# C210_0001_Serial_Interface.net
KiCad netlist of a schematic drawn in Altium Designer
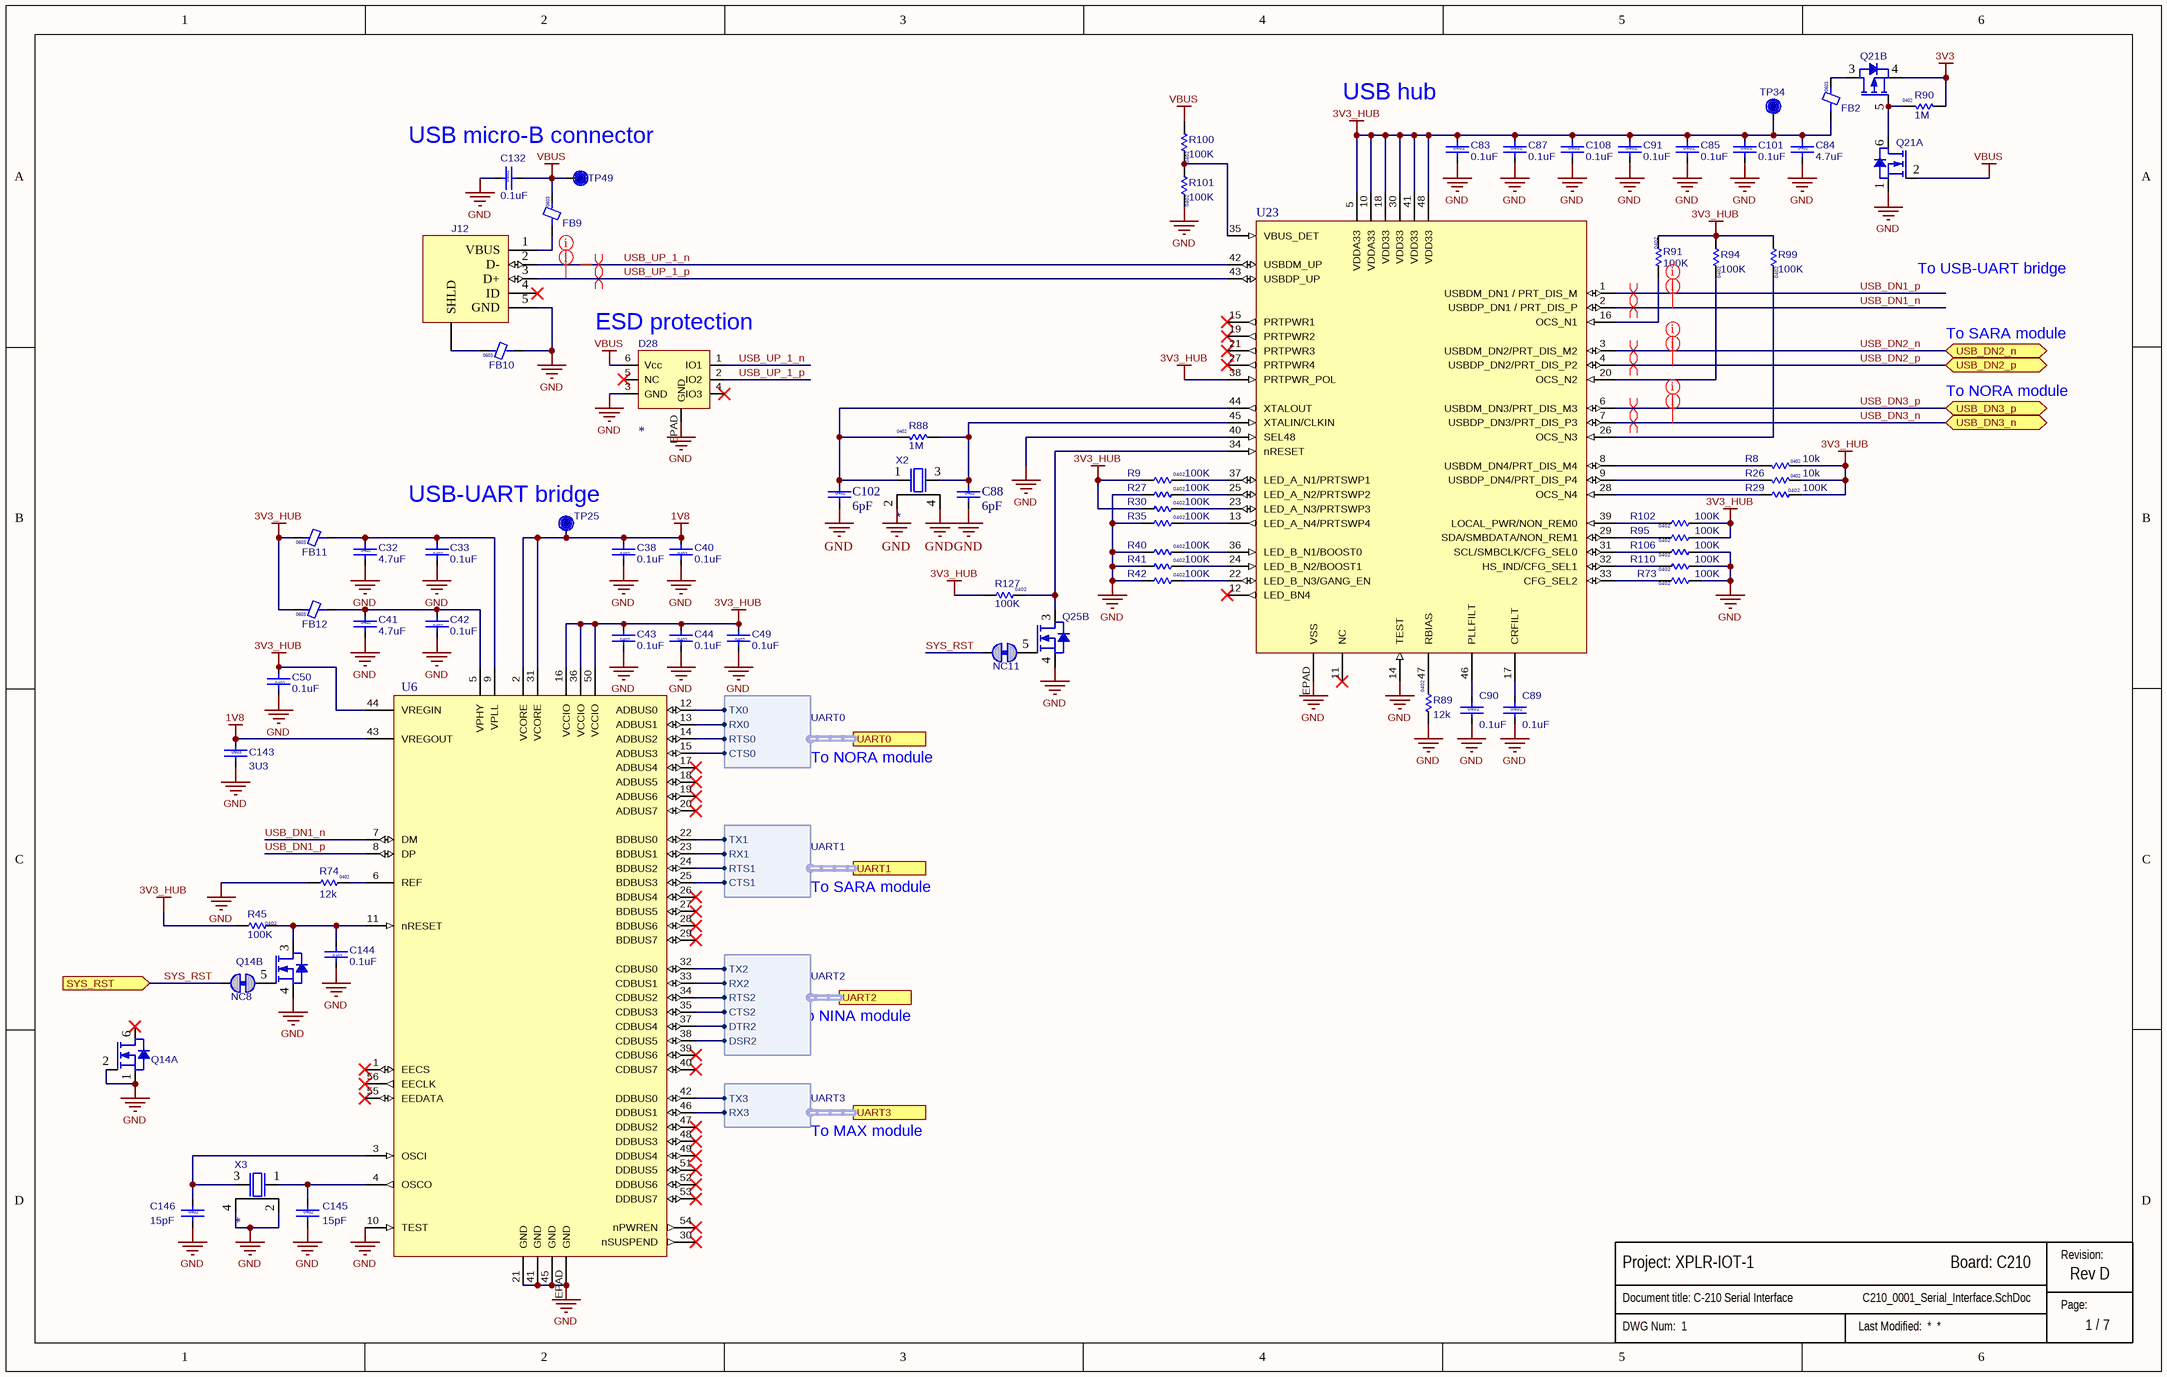
[diagram p0: C210_0001_Serial_Interface.SchDoc]

(export (version "E")
  (design (tool "Eeschema 10.0.6"))
  (components
    (comp (ref "C32")
      (value "4.7uF")
      (footprint "Cap 0402 HD")
      (description "Cap, Ceramic 4.7uF 10V 20% X5R 0402")
      (fields
        (field (name "SIZE") "0402")
        (field (name "PART NUMBER") "120-00020")
        (field (name "TOLERANCE") "+/- 20%")
      )
      (libsource (lib "Arena_Parts_DB_Lib") (part "Cap Chip"))
    )
    (comp (ref "C33")
      (value "0.1uF")
      (footprint "Cap 0402 HD")
      (description "Cap, Ceramic 0.1uF 10V 10% X5R 0402")
      (fields
        (field (name "SIZE") "0402")
        (field (name "PART NUMBER") "120-00016")
        (field (name "MANUFACTURER") "Murata Electronics North America")
      )
      (libsource (lib "Arena_Parts_DB_Lib") (part "Cap Chip"))
    )
    (comp (ref "C38")
      (value "0.1uF")
      (footprint "Cap 0402 HD")
      (description "Cap, Ceramic 0.1uF 10V 10% X5R 0402")
      (fields
        (field (name "SIZE") "0402")
        (field (name "PART NUMBER") "120-00016")
        (field (name "MANUFACTURER") "Murata Electronics North America")
      )
      (libsource (lib "Arena_Parts_DB_Lib") (part "Cap Chip"))
    )
    (comp (ref "C40")
      (value "0.1uF")
      (footprint "Cap 0402 HD")
      (description "Cap, Ceramic 0.1uF 10V 10% X5R 0402")
      (fields
        (field (name "SIZE") "0402")
        (field (name "PART NUMBER") "120-00016")
        (field (name "MANUFACTURER") "Murata Electronics North America")
      )
      (libsource (lib "Arena_Parts_DB_Lib") (part "Cap Chip"))
    )
    (comp (ref "C41")
      (value "4.7uF")
      (footprint "Cap 0402 HD")
      (description "Cap, Ceramic 4.7uF 10V 20% X5R 0402")
      (fields
        (field (name "SIZE") "0402")
        (field (name "PART NUMBER") "120-00020")
        (field (name "TOLERANCE") "+/- 20%")
      )
      (libsource (lib "Arena_Parts_DB_Lib") (part "Cap Chip"))
    )
    (comp (ref "C42")
      (value "0.1uF")
      (footprint "Cap 0402 HD")
      (description "Cap, Ceramic 0.1uF 10V 10% X5R 0402")
      (fields
        (field (name "SIZE") "0402")
        (field (name "PART NUMBER") "120-00016")
        (field (name "MANUFACTURER") "Murata Electronics North America")
      )
      (libsource (lib "Arena_Parts_DB_Lib") (part "Cap Chip"))
    )
    (comp (ref "C43")
      (value "0.1uF")
      (footprint "Cap 0402 HD")
      (description "Cap, Ceramic 0.1uF 10V 10% X5R 0402")
      (fields
        (field (name "SIZE") "0402")
        (field (name "PART NUMBER") "120-00016")
        (field (name "MANUFACTURER") "Murata Electronics North America")
      )
      (libsource (lib "Arena_Parts_DB_Lib") (part "Cap Chip"))
    )
    (comp (ref "C44")
      (value "0.1uF")
      (footprint "Cap 0402 HD")
      (description "Cap, Ceramic 0.1uF 10V 10% X5R 0402")
      (fields
        (field (name "SIZE") "0402")
        (field (name "PART NUMBER") "120-00016")
        (field (name "MANUFACTURER") "Murata Electronics North America")
      )
      (libsource (lib "Arena_Parts_DB_Lib") (part "Cap Chip"))
    )
    (comp (ref "C49")
      (value "0.1uF")
      (footprint "Cap 0402 HD")
      (description "Cap, Ceramic 0.1uF 10V 10% X5R 0402")
      (fields
        (field (name "SIZE") "0402")
        (field (name "PART NUMBER") "120-00016")
        (field (name "MANUFACTURER") "Murata Electronics North America")
      )
      (libsource (lib "Arena_Parts_DB_Lib") (part "Cap Chip"))
    )
    (comp (ref "C50")
      (value "0.1uF")
      (footprint "Cap 0402 HD")
      (description "Cap, Ceramic 0.1uF 10V 10% X5R 0402")
      (fields
        (field (name "SIZE") "0402")
        (field (name "PART NUMBER") "120-00016")
        (field (name "MANUFACTURER") "Murata Electronics North America")
      )
      (libsource (lib "Arena_Parts_DB_Lib") (part "Cap Chip"))
    )
    (comp (ref "C83")
      (value "0.1uF")
      (footprint "Cap 0402 HD")
      (description "Cap, Ceramic 0.1uF 10V 10% X5R 0402")
      (fields
        (field (name "SIZE") "0402")
        (field (name "PART NUMBER") "120-00016")
        (field (name "MANUFACTURER") "Murata Electronics North America")
      )
      (libsource (lib "Arena_Parts_DB_Lib") (part "Cap Chip"))
    )
    (comp (ref "C84")
      (value "4.7uF")
      (footprint "Cap 0402 HD")
      (description "Cap, Ceramic 4.7uF 10V 20% X5R 0402")
      (fields
        (field (name "SIZE") "0402")
        (field (name "PART NUMBER") "120-00020")
        (field (name "TOLERANCE") "+/- 20%")
      )
      (libsource (lib "Arena_Parts_DB_Lib") (part "Cap Chip"))
    )
    (comp (ref "C85")
      (value "0.1uF")
      (footprint "Cap 0402 HD")
      (description "Cap, Ceramic 0.1uF 10V 10% X5R 0402")
      (fields
        (field (name "SIZE") "0402")
        (field (name "PART NUMBER") "120-00016")
        (field (name "MANUFACTURER") "Murata Electronics North America")
      )
      (libsource (lib "Arena_Parts_DB_Lib") (part "Cap Chip"))
    )
    (comp (ref "C87")
      (value "0.1uF")
      (footprint "Cap 0402 HD")
      (description "Cap, Ceramic 0.1uF 10V 10% X5R 0402")
      (fields
        (field (name "SIZE") "0402")
        (field (name "PART NUMBER") "120-00016")
        (field (name "MANUFACTURER") "Murata Electronics North America")
      )
      (libsource (lib "Arena_Parts_DB_Lib") (part "Cap Chip"))
    )
    (comp (ref "C88")
      (value "6pF")
      (footprint "Cap 0402 HD")
      (description "Cap, Ceramic 6pF 50V NP0 0402  Tolerance = +/-0.5pF")
      (fields
        (field (name "SIZE") "0402")
        (field (name "PART NUMBER") "120-00048")
        (field (name "TOLERANCE") "Other")
      )
      (libsource (lib "Arena_Parts_DB_Lib") (part "Cap Chip"))
    )
    (comp (ref "C89")
      (value "0.1uF")
      (footprint "Cap 0402 HD")
      (description "Cap, Ceramic 0.1uF 10V 10% X5R 0402")
      (fields
        (field (name "SIZE") "0402")
        (field (name "PART NUMBER") "120-00016")
        (field (name "MANUFACTURER") "Murata Electronics North America")
      )
      (libsource (lib "Arena_Parts_DB_Lib") (part "Cap Chip"))
    )
    (comp (ref "C90")
      (value "0.1uF")
      (footprint "Cap 0402 HD")
      (description "Cap, Ceramic 0.1uF 10V 10% X5R 0402")
      (fields
        (field (name "SIZE") "0402")
        (field (name "PART NUMBER") "120-00016")
        (field (name "MANUFACTURER") "Murata Electronics North America")
      )
      (libsource (lib "Arena_Parts_DB_Lib") (part "Cap Chip"))
    )
    (comp (ref "C91")
      (value "0.1uF")
      (footprint "Cap 0402 HD")
      (description "Cap, Ceramic 0.1uF 10V 10% X5R 0402")
      (fields
        (field (name "SIZE") "0402")
        (field (name "PART NUMBER") "120-00016")
        (field (name "MANUFACTURER") "Murata Electronics North America")
      )
      (libsource (lib "Arena_Parts_DB_Lib") (part "Cap Chip"))
    )
    (comp (ref "C101")
      (value "0.1uF")
      (footprint "Cap 0402 HD")
      (description "Cap, Ceramic 0.1uF 10V 10% X5R 0402")
      (fields
        (field (name "SIZE") "0402")
        (field (name "PART NUMBER") "120-00016")
        (field (name "MANUFACTURER") "Murata Electronics North America")
      )
      (libsource (lib "Arena_Parts_DB_Lib") (part "Cap Chip"))
    )
    (comp (ref "C102")
      (value "6pF")
      (footprint "Cap 0402 HD")
      (description "Cap, Ceramic 6pF 50V NP0 0402  Tolerance = +/-0.5pF")
      (fields
        (field (name "SIZE") "0402")
        (field (name "PART NUMBER") "120-00048")
        (field (name "TOLERANCE") "Other")
      )
      (libsource (lib "Arena_Parts_DB_Lib") (part "Cap Chip"))
    )
    (comp (ref "C108")
      (value "0.1uF")
      (footprint "Cap 0402 HD")
      (description "Cap, Ceramic 0.1uF 10V 10% X5R 0402")
      (fields
        (field (name "SIZE") "0402")
        (field (name "PART NUMBER") "120-00016")
        (field (name "MANUFACTURER") "Murata Electronics North America")
      )
      (libsource (lib "Arena_Parts_DB_Lib") (part "Cap Chip"))
    )
    (comp (ref "C132")
      (value "0.1uF")
      (footprint "Cap 0402 HD")
      (description "Cap, Ceramic 0.1uF 10V 10% X5R 0402")
      (fields
        (field (name "SIZE") "0402")
        (field (name "PART NUMBER") "120-00016")
        (field (name "MANUFACTURER") "Murata Electronics North America")
      )
      (libsource (lib "Arena_Parts_DB_Lib") (part "Cap Chip"))
    )
    (comp (ref "C143")
      (value "3U3")
      (footprint "Cap 0603 HD")
      (description "CAP CER X5R 0603 3U3 10% 10V")
      (fields
        (field (name "SIZE") "0603")
        (field (name "PART NUMBER") "UBXH01-0000035")
        (field (name "TOLERANCE") "10%")
        (field (name "EDITOR") "dario.antonaz")
        (field (name "RELEASED BY") "karel.cotic")
      )
      (libsource (lib "UBX_Parts_DB_Lib") (part "Cap Chip"))
    )
    (comp (ref "C144")
      (value "0.1uF")
      (footprint "Cap 0402 HD")
      (description "Cap, Ceramic 0.1uF 10V 10% X5R 0402")
      (fields
        (field (name "SIZE") "0402")
        (field (name "PART NUMBER") "120-00016")
        (field (name "MANUFACTURER") "Murata Electronics North America")
      )
      (libsource (lib "Arena_Parts_DB_Lib") (part "Cap Chip"))
    )
    (comp (ref "C145")
      (value "15pF")
      (footprint "Cap 0402 HD")
      (description "Capacitor, Ceramic, 15pF 5%, 50V, NPO, 0402")
      (fields
        (field (name "SIZE") "0402")
        (field (name "PART NUMBER") "120-00110")
        (field (name "TOLERANCE") "+/- 5%")
      )
      (libsource (lib "Arena_Parts_DB_Lib") (part "Cap Chip"))
    )
    (comp (ref "C146")
      (value "15pF")
      (footprint "Cap 0402 HD")
      (description "Capacitor, Ceramic, 15pF 5%, 50V, NPO, 0402")
      (fields
        (field (name "SIZE") "0402")
        (field (name "PART NUMBER") "120-00110")
        (field (name "TOLERANCE") "+/- 5%")
      )
      (libsource (lib "Arena_Parts_DB_Lib") (part "Cap Chip"))
    )
    (comp (ref "D28")
      (value "~")
      (footprint "TPD3E001DRSR")
      (description "TVS Diode, ESD High Speed 3-Channel Array, WSON-6, 3mmX3mm")
      (fields (field (name "VOLTAGE") "5.5V") (field (name "MANUFACTURER P/N") "*"))
      (libsource (lib "TPD3E001DRSR") (part "TPD3E001"))
    )
    (comp (ref "FB2")
      (value "BLM18EG221SN1")
      (footprint "BLM18EG221SN1")
      (description "Ferrite Bead, 220ohm @ 100MHz, 2A, 0603")
      (fields (field (name "VOLTAGE") "None") (field (name "SIZE") "0603"))
      (libsource (lib "BLM18EG221SN1") (part "BLM18EG221SN1"))
    )
    (comp (ref "FB9")
      (value "BLM18EG221SN1")
      (footprint "BLM18EG221SN1")
      (description "Ferrite Bead, 220ohm @ 100MHz, 2A, 0603")
      (fields (field (name "VOLTAGE") "None") (field (name "SIZE") "0603"))
      (libsource (lib "BLM18EG221SN1") (part "BLM18EG221SN1"))
    )
    (comp (ref "FB10")
      (value "BLM18EG221SN1")
      (footprint "BLM18EG221SN1")
      (description "Ferrite Bead, 220ohm @ 100MHz, 2A, 0603")
      (fields (field (name "VOLTAGE") "None") (field (name "SIZE") "0603"))
      (libsource (lib "BLM18EG221SN1") (part "BLM18EG221SN1"))
    )
    (comp (ref "FB11")
      (value "BLM18EG221SN1")
      (footprint "BLM18EG221SN1")
      (description "Ferrite Bead, 220ohm @ 100MHz, 2A, 0603")
      (fields (field (name "VOLTAGE") "None") (field (name "SIZE") "0603"))
      (libsource (lib "BLM18EG221SN1") (part "BLM18EG221SN1"))
    )
    (comp (ref "FB12")
      (value "BLM18EG221SN1")
      (footprint "BLM18EG221SN1")
      (description "Ferrite Bead, 220ohm @ 100MHz, 2A, 0603")
      (fields (field (name "VOLTAGE") "None") (field (name "SIZE") "0603"))
      (libsource (lib "BLM18EG221SN1") (part "BLM18EG221SN1"))
    )
    (comp (ref "J12")
      (value "130-00008")
      (footprint "USB_Micro_RA_W-2TABS")
      (description "USB Micro B Receptacle, Right Angle SMT with 2 TH Tabs, 0.65mm")
      (fields (field (name "MANUFACTURER") "FCI"))
      (libsource (lib "Arena_Lib") (part "USB_W-Shield"))
    )
    (comp (ref "NC8")
      (value "Solderbridge-ShortDNP")
      (footprint "Solderbridge-Short")
      (description "Solderbridge-Short")
      (fields (field (name "ADDED BY") "Paul B"))
      (libsource (lib "PCB_Misc") (part "Solderbridge-Short"))
    )
    (comp (ref "NC11")
      (value "Solderbridge-ShortDNP")
      (footprint "Solderbridge-Short")
      (description "Solderbridge-Short")
      (fields (field (name "ADDED BY") "Paul B"))
      (libsource (lib "PCB_Misc") (part "Solderbridge-Short"))
    )
    (comp (ref "Q14")
      (value "140-00016")
      (footprint "SOT-563")
      (description "MOSFET 2N-CH 20V 0.8A, SOT-563")
      (fields (field (name "VOLTAGE") "20V"))
      (libsource (lib "Arena_Parts_DB_Lib") (part "MOSFET-N-Dual"))
    )
    (comp (ref "Q21")
      (value "140-00030")
      (footprint "SOT-563")
      (description "MOSFET N/P-CH 20V SOT-563, 540 mA, −430 mA")
      (fields (field (name "VOLTAGE") "20V"))
      (libsource (lib "Arena_Parts_DB_Lib") (part "MOSFET-N-P_Pair"))
    )
    (comp (ref "Q25")
      (value "140-00016")
      (footprint "SOT-563")
      (description "MOSFET 2N-CH 20V 0.8A, SOT-563")
      (fields (field (name "VOLTAGE") "20V"))
      (libsource (lib "Arena_Parts_DB_Lib") (part "MOSFET-N-Dual"))
    )
    (comp (ref "R8")
      (value "10k")
      (footprint "RES 0402 HD")
      (description "Resistor 10k ohm 1% 1/16W, 0402")
      (fields
        (field (name "SIZE") "0402")
        (field (name "PART NUMBER") "180-00024")
        (field (name "POWER") "1/16W")
      )
      (libsource (lib "Arena_Parts_DB_Lib") (part "Res sm"))
    )
    (comp (ref "R9")
      (value "100K")
      (footprint "RES 0402 HD")
      (description "Resistor 100K ohm 1% 1/16W, 0402")
      (fields
        (field (name "SIZE") "0402")
        (field (name "PART NUMBER") "180-00093")
        (field (name "POWER") "1/16W")
      )
      (libsource (lib "Arena_Parts_DB_Lib") (part "Res sm"))
    )
    (comp (ref "R26")
      (value "10k")
      (footprint "RES 0402 HD")
      (description "Resistor 10k ohm 1% 1/16W, 0402")
      (fields
        (field (name "SIZE") "0402")
        (field (name "PART NUMBER") "180-00024")
        (field (name "POWER") "1/16W")
      )
      (libsource (lib "Arena_Parts_DB_Lib") (part "Res sm"))
    )
    (comp (ref "R27")
      (value "100K")
      (footprint "RES 0402 HD")
      (description "Resistor 100K ohm 1% 1/16W, 0402")
      (fields
        (field (name "SIZE") "0402")
        (field (name "PART NUMBER") "180-00093")
        (field (name "POWER") "1/16W")
      )
      (libsource (lib "Arena_Parts_DB_Lib") (part "Res sm"))
    )
    (comp (ref "R29")
      (value "100K")
      (footprint "RES 0402 HD")
      (description "Resistor 100K ohm 1% 1/16W, 0402")
      (fields
        (field (name "SIZE") "0402")
        (field (name "PART NUMBER") "180-00093")
        (field (name "POWER") "1/16W")
      )
      (libsource (lib "Arena_Parts_DB_Lib") (part "Res sm"))
    )
    (comp (ref "R30")
      (value "100K")
      (footprint "RES 0402 HD")
      (description "Resistor 100K ohm 1% 1/16W, 0402")
      (fields
        (field (name "SIZE") "0402")
        (field (name "PART NUMBER") "180-00093")
        (field (name "POWER") "1/16W")
      )
      (libsource (lib "Arena_Parts_DB_Lib") (part "Res sm"))
    )
    (comp (ref "R35")
      (value "100K")
      (footprint "RES 0402 HD")
      (description "Resistor 100K ohm 1% 1/16W, 0402")
      (fields
        (field (name "SIZE") "0402")
        (field (name "PART NUMBER") "180-00093")
        (field (name "POWER") "1/16W")
      )
      (libsource (lib "Arena_Parts_DB_Lib") (part "Res sm"))
    )
    (comp (ref "R40")
      (value "100K")
      (footprint "RES 0402 HD")
      (description "Resistor 100K ohm 1% 1/16W, 0402")
      (fields
        (field (name "SIZE") "0402")
        (field (name "PART NUMBER") "180-00093")
        (field (name "POWER") "1/16W")
      )
      (libsource (lib "Arena_Parts_DB_Lib") (part "Res sm"))
    )
    (comp (ref "R41")
      (value "100K")
      (footprint "RES 0402 HD")
      (description "Resistor 100K ohm 1% 1/16W, 0402")
      (fields
        (field (name "SIZE") "0402")
        (field (name "PART NUMBER") "180-00093")
        (field (name "POWER") "1/16W")
      )
      (libsource (lib "Arena_Parts_DB_Lib") (part "Res sm"))
    )
    (comp (ref "R42")
      (value "100K")
      (footprint "RES 0402 HD")
      (description "Resistor 100K ohm 1% 1/16W, 0402")
      (fields
        (field (name "SIZE") "0402")
        (field (name "PART NUMBER") "180-00093")
        (field (name "POWER") "1/16W")
      )
      (libsource (lib "Arena_Parts_DB_Lib") (part "Res sm"))
    )
    (comp (ref "R45")
      (value "100K")
      (footprint "RES 0402 HD")
      (description "Resistor 100K ohm 1% 1/16W, 0402")
      (fields
        (field (name "SIZE") "0402")
        (field (name "PART NUMBER") "180-00093")
        (field (name "POWER") "1/16W")
      )
      (libsource (lib "Arena_Parts_DB_Lib") (part "Res sm"))
    )
    (comp (ref "R73")
      (value "100K")
      (footprint "RES 0402 HD")
      (description "Resistor 100K ohm 1% 1/16W, 0402")
      (fields
        (field (name "SIZE") "0402")
        (field (name "PART NUMBER") "180-00093")
        (field (name "POWER") "1/16W")
      )
      (libsource (lib "Arena_Parts_DB_Lib") (part "Res sm"))
    )
    (comp (ref "R74")
      (value "12k")
      (footprint "RES 0402 HD")
      (description "Resistor 12k ohm 1% 1/16W 0402")
      (fields
        (field (name "SIZE") "0402")
        (field (name "PART NUMBER") "180-00096")
        (field (name "POWER") "1/16W")
      )
      (libsource (lib "Arena_Parts_DB_Lib") (part "Res sm"))
    )
    (comp (ref "R88")
      (value "1M")
      (footprint "RES 0402 HD")
      (description "Resistor 1M ohm 1%, 1/16W, 0402")
      (fields
        (field (name "SIZE") "0402")
        (field (name "PART NUMBER") "180-00054")
        (field (name "POWER") "1/16W")
      )
      (libsource (lib "Arena_Parts_DB_Lib") (part "Res sm"))
    )
    (comp (ref "R89")
      (value "12k")
      (footprint "RES 0402 HD")
      (description "Resistor 12k ohm 1% 1/16W 0402")
      (fields
        (field (name "SIZE") "0402")
        (field (name "PART NUMBER") "180-00096")
        (field (name "POWER") "1/16W")
      )
      (libsource (lib "Arena_Parts_DB_Lib") (part "Res sm"))
    )
    (comp (ref "R90")
      (value "1M")
      (footprint "RES 0402 HD")
      (description "Resistor 1M ohm 1%, 1/16W, 0402")
      (fields
        (field (name "SIZE") "0402")
        (field (name "PART NUMBER") "180-00054")
        (field (name "POWER") "1/16W")
      )
      (libsource (lib "Arena_Parts_DB_Lib") (part "Res sm"))
    )
    (comp (ref "R91")
      (value "100K")
      (footprint "RES 0402 HD")
      (description "Resistor 100K ohm 1% 1/16W, 0402")
      (fields
        (field (name "SIZE") "0402")
        (field (name "PART NUMBER") "180-00093")
        (field (name "POWER") "1/16W")
      )
      (libsource (lib "Arena_Parts_DB_Lib") (part "Res sm"))
    )
    (comp (ref "R94")
      (value "100K")
      (footprint "RES 0402 HD")
      (description "Resistor 100K ohm 1% 1/16W, 0402")
      (fields
        (field (name "SIZE") "0402")
        (field (name "PART NUMBER") "180-00093")
        (field (name "POWER") "1/16W")
      )
      (libsource (lib "Arena_Parts_DB_Lib") (part "Res sm"))
    )
    (comp (ref "R95")
      (value "100K")
      (footprint "RES 0402 HD")
      (description "Resistor 100K ohm 1% 1/16W, 0402")
      (fields
        (field (name "SIZE") "0402")
        (field (name "PART NUMBER") "180-00093")
        (field (name "POWER") "1/16W")
      )
      (libsource (lib "Arena_Parts_DB_Lib") (part "Res sm"))
    )
    (comp (ref "R99")
      (value "100K")
      (footprint "RES 0402 HD")
      (description "Resistor 100K ohm 1% 1/16W, 0402")
      (fields
        (field (name "SIZE") "0402")
        (field (name "PART NUMBER") "180-00093")
        (field (name "POWER") "1/16W")
      )
      (libsource (lib "Arena_Parts_DB_Lib") (part "Res sm"))
    )
    (comp (ref "R100")
      (value "100K")
      (footprint "RES 0402 HD")
      (description "Resistor 100K ohm 1% 1/16W, 0402")
      (fields
        (field (name "SIZE") "0402")
        (field (name "PART NUMBER") "180-00093")
        (field (name "POWER") "1/16W")
      )
      (libsource (lib "Arena_Parts_DB_Lib") (part "Res sm"))
    )
    (comp (ref "R101")
      (value "100K")
      (footprint "RES 0402 HD")
      (description "Resistor 100K ohm 1% 1/16W, 0402")
      (fields
        (field (name "SIZE") "0402")
        (field (name "PART NUMBER") "180-00093")
        (field (name "POWER") "1/16W")
      )
      (libsource (lib "Arena_Parts_DB_Lib") (part "Res sm"))
    )
    (comp (ref "R102")
      (value "100K")
      (footprint "RES 0402 HD")
      (description "Resistor 100K ohm 1% 1/16W, 0402")
      (fields
        (field (name "SIZE") "0402")
        (field (name "PART NUMBER") "180-00093")
        (field (name "POWER") "1/16W")
      )
      (libsource (lib "Arena_Parts_DB_Lib") (part "Res sm"))
    )
    (comp (ref "R106")
      (value "100K")
      (footprint "RES 0402 HD")
      (description "Resistor 100K ohm 1% 1/16W, 0402")
      (fields
        (field (name "SIZE") "0402")
        (field (name "PART NUMBER") "180-00093")
        (field (name "POWER") "1/16W")
      )
      (libsource (lib "Arena_Parts_DB_Lib") (part "Res sm"))
    )
    (comp (ref "R110")
      (value "100K")
      (footprint "RES 0402 HD")
      (description "Resistor 100K ohm 1% 1/16W, 0402")
      (fields
        (field (name "SIZE") "0402")
        (field (name "PART NUMBER") "180-00093")
        (field (name "POWER") "1/16W")
      )
      (libsource (lib "Arena_Parts_DB_Lib") (part "Res sm"))
    )
    (comp (ref "R127")
      (value "100K")
      (footprint "RES 0402 HD")
      (description "Resistor 100K ohm 1% 1/16W, 0402")
      (fields
        (field (name "SIZE") "0402")
        (field (name "PART NUMBER") "180-00093")
        (field (name "POWER") "1/16W")
      )
      (libsource (lib "Arena_Parts_DB_Lib") (part "Res sm"))
    )
    (comp (ref "TP25")
      (value "TP")
      (footprint "TP12R")
      (description "Testpoint, Round 1.0mm Dia")
      (fields
        (field (name "PART NUMBER") "TP10R")
        (field (name "ADDED BY") "Jeremy D")
        (field (name "CHECKED BY") "Paul B")
      )
      (libsource (lib "PCB_Misc") (part "TP_R"))
    )
    (comp (ref "TP34")
      (value "TP")
      (footprint "TP12R")
      (description "Testpoint, Round 1.0mm Dia")
      (fields
        (field (name "PART NUMBER") "TP10R")
        (field (name "ADDED BY") "Jeremy D")
        (field (name "CHECKED BY") "Paul B")
      )
      (libsource (lib "PCB_Misc") (part "TP_R"))
    )
    (comp (ref "TP49")
      (value "TP")
      (footprint "TP12R")
      (description "Testpoint, Round 1.0mm Dia")
      (fields
        (field (name "PART NUMBER") "TP10R")
        (field (name "ADDED BY") "Jeremy D")
        (field (name "CHECKED BY") "Paul B")
      )
      (libsource (lib "PCB_Misc") (part "TP_R"))
    )
    (comp (ref "U6")
      (value "~")
      (footprint "QFN0.5P8.0x8.0-56Pin_EPAD")
      (description "IC, SMT, UART/SERIAL BRIDGE, QUAD, USB 2.0, FULL HANDSHAKE, 12MBps, 2.97-3.63V, 8mmx8mm QFN56")
      (fields (field (name "VOLTAGE") "2.97-3.63V"))
      (libsource (lib "FT4232H") (part "FT4232H"))
    )
    (comp (ref "U23")
      (value "USB2514-HZH")
      (footprint "QFN0.5P7.0x7.0-48Pin_EPAD")
      (description "4-PORT USB 2.0 HUB CTRLR, QFN-48, 7.0mmx7.0mm")
      (libsource (lib "USB2514-HZH") (part "USB2514-HZH"))
    )
    (comp (ref "X2")
      (value "100-00017")
      (footprint "XTAL_2520_HD")
      (description "Crystal, 24.0000MHz, 20ppm, 10pF, 100 Ohm, -20Â°C - 70Â°C, SMT 4 Pin 2520")
      (fields (field (name "ALTIUM_VALUE") "*") (field (name "VOLTAGE") "None"))
      (libsource (lib "Arena_Parts_DB_Lib") (part "XTAL_4Pin"))
    )
    (comp (ref "X3")
      (value "100-00033")
      (footprint "XTAL_2520")
      (description "12MHz ±10ppm Crystal 8pF 125 Ohm -40°C ~ 85°C Surface Mount 4-SMD, No Lead")
      (fields (field (name "ALTIUM_VALUE") "*") (field (name "VOLTAGE") "None"))
      (libsource (lib "Arena_Parts_DB_Lib") (part "XTAL_4Pin"))
    )
  )
  (nets
    (net (code "5") (name "/CTS0") (class "Default")
      (node (ref "U6") (pin "15") (pinfunction "ADBUS3_15") (pintype "bidirectional"))
    )
    (net (code "6") (name "/CTS1") (class "Default")
      (node (ref "U6") (pin "25") (pinfunction "BDBUS3_25") (pintype "bidirectional"))
    )
    (net (code "7") (name "/CTS2") (class "Default")
      (node (ref "U6") (pin "35") (pinfunction "CDBUS3_35") (pintype "bidirectional"))
    )
    (net (code "8") (name "/DSR2") (class "Default")
      (node (ref "U6") (pin "38") (pinfunction "CDBUS5_38") (pintype "bidirectional"))
    )
    (net (code "9") (name "/DTR2") (class "Default")
      (node (ref "U6") (pin "37") (pinfunction "CDBUS4_37") (pintype "bidirectional"))
    )
    (net (code "10") (name "/RTS0") (class "Default")
      (node (ref "U6") (pin "14") (pinfunction "ADBUS2_14") (pintype "bidirectional"))
    )
    (net (code "11") (name "/RTS1") (class "Default")
      (node (ref "U6") (pin "24") (pinfunction "BDBUS2_24") (pintype "bidirectional"))
    )
    (net (code "12") (name "/RTS2") (class "Default")
      (node (ref "U6") (pin "34") (pinfunction "CDBUS2_34") (pintype "bidirectional"))
    )
    (net (code "13") (name "/RX0") (class "Default")
      (node (ref "U6") (pin "13") (pinfunction "ADBUS1_13") (pintype "bidirectional"))
    )
    (net (code "14") (name "/RX1") (class "Default")
      (node (ref "U6") (pin "23") (pinfunction "BDBUS1_23") (pintype "bidirectional"))
    )
    (net (code "15") (name "/RX2") (class "Default")
      (node (ref "U6") (pin "33") (pinfunction "CDBUS1_33") (pintype "bidirectional"))
    )
    (net (code "16") (name "/RX3") (class "Default")
      (node (ref "U6") (pin "46") (pinfunction "DDBUS1_46") (pintype "bidirectional"))
    )
    (net (code "17") (name "/SYS_RST") (class "Default")
      (node (ref "NC11") (pin "2") (pinfunction "2_2") (pintype "passive"))
      (node (ref "NC8") (pin "2") (pinfunction "2_2") (pintype "passive"))
    )
    (net (code "18") (name "/TX0") (class "Default")
      (node (ref "U6") (pin "12") (pinfunction "ADBUS0_12") (pintype "bidirectional"))
    )
    (net (code "19") (name "/TX1") (class "Default")
      (node (ref "U6") (pin "22") (pinfunction "BDBUS0_22") (pintype "bidirectional"))
    )
    (net (code "20") (name "/TX2") (class "Default")
      (node (ref "U6") (pin "32") (pinfunction "CDBUS0_32") (pintype "bidirectional"))
    )
    (net (code "21") (name "/TX3") (class "Default")
      (node (ref "U6") (pin "42") (pinfunction "DDBUS0_42") (pintype "bidirectional"))
    )
    (net (code "22") (name "/USB_DN1_n") (class "Default")
      (node (ref "U23") (pin "2") (pinfunction "USBDP_DN1_/_PRT_DIS_P_2") (pintype "bidirectional"))
      (node (ref "U6") (pin "7") (pinfunction "DM_7") (pintype "bidirectional"))
    )
    (net (code "23") (name "/USB_DN1_p") (class "Default")
      (node (ref "U23") (pin "1") (pinfunction "USBDM_DN1_/_PRT_DIS_M_1") (pintype "bidirectional"))
      (node (ref "U6") (pin "8") (pinfunction "DP_8") (pintype "bidirectional"))
    )
    (net (code "24") (name "/USB_DN2_n") (class "Default")
      (node (ref "U23") (pin "3") (pinfunction "USBDM_DN2/PRT_DIS_M2_3") (pintype "bidirectional"))
    )
    (net (code "25") (name "/USB_DN2_p") (class "Default")
      (node (ref "U23") (pin "4") (pinfunction "USBDP_DN2/PRT_DIS_P2_4") (pintype "bidirectional"))
    )
    (net (code "26") (name "/USB_DN3_n") (class "Default")
      (node (ref "U23") (pin "7") (pinfunction "USBDP_DN3/PRT_DIS_P3_7") (pintype "bidirectional"))
    )
    (net (code "27") (name "/USB_DN3_p") (class "Default")
      (node (ref "U23") (pin "6") (pinfunction "USBDM_DN3/PRT_DIS_M3_6") (pintype "bidirectional"))
    )
    (net (code "28") (name "/USB_UP_1_n") (class "Default")
      (node (ref "D28") (pin "1") (pinfunction "IO1_1") (pintype "passive"))
      (node (ref "J12") (pin "2") (pinfunction "D-_2") (pintype "bidirectional"))
      (node (ref "U23") (pin "42") (pinfunction "USBDM_UP_42") (pintype "bidirectional"))
    )
    (net (code "29") (name "/USB_UP_1_p") (class "Default")
      (node (ref "D28") (pin "2") (pinfunction "IO2_2") (pintype "passive"))
      (node (ref "J12") (pin "3") (pinfunction "D+_3") (pintype "bidirectional"))
      (node (ref "U23") (pin "43") (pinfunction "USBDP_UP_43") (pintype "bidirectional"))
    )
    (net (code "34") (name "1V8") (class "Default")
      (node (ref "C143") (pin "1") (pinfunction "1_1") (pintype "passive"))
      (node (ref "C38") (pin "2") (pinfunction "2_2") (pintype "passive"))
      (node (ref "C40") (pin "2") (pinfunction "2_2") (pintype "passive"))
      (node (ref "TP25") (pin "1") (pintype "passive"))
      (node (ref "U6") (pin "2") (pinfunction "VCORE_2") (pintype "power_in"))
      (node (ref "U6") (pin "31") (pinfunction "VCORE_31") (pintype "power_in"))
      (node (ref "U6") (pin "43") (pinfunction "VREGOUT_43") (pintype "power_in"))
    )
    (net (code "35") (name "3V3") (class "Default")
      (node (ref "Q21") (pin "4") (pinfunction "S2_4") (pintype "passive"))
      (node (ref "R90") (pin "1") (pinfunction "1_1") (pintype "passive"))
    )
    (net (code "36") (name "3V3_HUB") (class "Default")
      (node (ref "C101") (pin "1") (pinfunction "1_1") (pintype "passive"))
      (node (ref "C108") (pin "1") (pinfunction "1_1") (pintype "passive"))
      (node (ref "C43") (pin "2") (pinfunction "2_2") (pintype "passive"))
      (node (ref "C44") (pin "2") (pinfunction "2_2") (pintype "passive"))
      (node (ref "C49") (pin "2") (pinfunction "2_2") (pintype "passive"))
      (node (ref "C50") (pin "2") (pinfunction "2_2") (pintype "passive"))
      (node (ref "C83") (pin "1") (pinfunction "1_1") (pintype "passive"))
      (node (ref "C84") (pin "1") (pinfunction "1_1") (pintype "passive"))
      (node (ref "C85") (pin "1") (pinfunction "1_1") (pintype "passive"))
      (node (ref "C87") (pin "1") (pinfunction "1_1") (pintype "passive"))
      (node (ref "C91") (pin "1") (pinfunction "1_1") (pintype "passive"))
      (node (ref "FB11") (pin "2") (pinfunction "2_2") (pintype "passive"))
      (node (ref "FB12") (pin "2") (pinfunction "2_2") (pintype "passive"))
      (node (ref "FB2") (pin "1") (pinfunction "1_1") (pintype "passive"))
      (node (ref "R102") (pin "1") (pinfunction "1_1") (pintype "passive"))
      (node (ref "R127") (pin "1") (pinfunction "1_1") (pintype "passive"))
      (node (ref "R26") (pin "2") (pinfunction "2_2") (pintype "passive"))
      (node (ref "R29") (pin "2") (pinfunction "2_2") (pintype "passive"))
      (node (ref "R30") (pin "1") (pinfunction "1_1") (pintype "passive"))
      (node (ref "R45") (pin "1") (pinfunction "1_1") (pintype "passive"))
      (node (ref "R8") (pin "2") (pinfunction "2_2") (pintype "passive"))
      (node (ref "R9") (pin "1") (pinfunction "1_1") (pintype "passive"))
      (node (ref "R91") (pin "2") (pinfunction "2_2") (pintype "passive"))
      (node (ref "R94") (pin "1") (pinfunction "1_1") (pintype "passive"))
      (node (ref "R95") (pin "1") (pinfunction "1_1") (pintype "passive"))
      (node (ref "R99") (pin "1") (pinfunction "1_1") (pintype "passive"))
      (node (ref "TP34") (pin "1") (pintype "passive"))
      (node (ref "U23") (pin "10") (pinfunction "VDDA33_10") (pintype "passive"))
      (node (ref "U23") (pin "18") (pinfunction "VDD33_18") (pintype "power_in"))
      (node (ref "U23") (pin "30") (pinfunction "VDD33_30") (pintype "power_in"))
      (node (ref "U23") (pin "38") (pinfunction "PRTPWR_POL_38") (pintype "input"))
      (node (ref "U23") (pin "41") (pinfunction "VDD33_41") (pintype "power_in"))
      (node (ref "U23") (pin "48") (pinfunction "VDD33_48") (pintype "power_in"))
      (node (ref "U23") (pin "5") (pinfunction "VDDA33_5") (pintype "passive"))
      (node (ref "U6") (pin "16") (pinfunction "VCCIO_16") (pintype "power_in"))
      (node (ref "U6") (pin "36") (pinfunction "VCCIO_36") (pintype "power_in"))
      (node (ref "U6") (pin "44") (pinfunction "VREGIN_44") (pintype "power_in"))
      (node (ref "U6") (pin "50") (pinfunction "VCCIO_50") (pintype "power_in"))
    )
    (net (code "37") (name "GND") (class "Default")
      (node (ref "C101") (pin "2") (pinfunction "2_2") (pintype "passive"))
      (node (ref "C102") (pin "2") (pinfunction "2_2") (pintype "passive"))
      (node (ref "C108") (pin "2") (pinfunction "2_2") (pintype "passive"))
      (node (ref "C132") (pin "1") (pinfunction "1_1") (pintype "passive"))
      (node (ref "C143") (pin "2") (pinfunction "2_2") (pintype "passive"))
      (node (ref "C144") (pin "1") (pinfunction "1_1") (pintype "passive"))
      (node (ref "C145") (pin "2") (pinfunction "2_2") (pintype "passive"))
      (node (ref "C146") (pin "2") (pinfunction "2_2") (pintype "passive"))
      (node (ref "C32") (pin "2") (pinfunction "2_2") (pintype "passive"))
      (node (ref "C33") (pin "1") (pinfunction "1_1") (pintype "passive"))
      (node (ref "C38") (pin "1") (pinfunction "1_1") (pintype "passive"))
      (node (ref "C40") (pin "1") (pinfunction "1_1") (pintype "passive"))
      (node (ref "C41") (pin "2") (pinfunction "2_2") (pintype "passive"))
      (node (ref "C42") (pin "1") (pinfunction "1_1") (pintype "passive"))
      (node (ref "C43") (pin "1") (pinfunction "1_1") (pintype "passive"))
      (node (ref "C44") (pin "1") (pinfunction "1_1") (pintype "passive"))
      (node (ref "C49") (pin "1") (pinfunction "1_1") (pintype "passive"))
      (node (ref "C50") (pin "1") (pinfunction "1_1") (pintype "passive"))
      (node (ref "C83") (pin "2") (pinfunction "2_2") (pintype "passive"))
      (node (ref "C84") (pin "2") (pinfunction "2_2") (pintype "passive"))
      (node (ref "C85") (pin "2") (pinfunction "2_2") (pintype "passive"))
      (node (ref "C87") (pin "2") (pinfunction "2_2") (pintype "passive"))
      (node (ref "C88") (pin "2") (pinfunction "2_2") (pintype "passive"))
      (node (ref "C89") (pin "2") (pinfunction "2_2") (pintype "passive"))
      (node (ref "C90") (pin "2") (pinfunction "2_2") (pintype "passive"))
      (node (ref "C91") (pin "2") (pinfunction "2_2") (pintype "passive"))
      (node (ref "D28") (pin "3") (pinfunction "GND_3") (pintype "power_in"))
      (node (ref "D28") (pin "EPAD") (pinfunction "GND_EPAD") (pintype "power_in"))
      (node (ref "FB10") (pin "1") (pinfunction "1_1") (pintype "passive"))
      (node (ref "J12") (pin "5") (pinfunction "GND_5") (pintype "power_in"))
      (node (ref "Q14") (pin "1") (pinfunction "S1_1") (pintype "passive"))
      (node (ref "Q14") (pin "2") (pinfunction "G1_2") (pintype "passive"))
      (node (ref "Q14") (pin "4") (pinfunction "S2_4") (pintype "passive"))
      (node (ref "Q21") (pin "1") (pinfunction "S1_1") (pintype "passive"))
      (node (ref "Q25") (pin "4") (pinfunction "S2_4") (pintype "passive"))
      (node (ref "R101") (pin "2") (pinfunction "2_2") (pintype "passive"))
      (node (ref "R106") (pin "2") (pinfunction "2_2") (pintype "passive"))
      (node (ref "R110") (pin "2") (pinfunction "2_2") (pintype "passive"))
      (node (ref "R27") (pin "1") (pinfunction "1_1") (pintype "passive"))
      (node (ref "R35") (pin "1") (pinfunction "1_1") (pintype "passive"))
      (node (ref "R40") (pin "1") (pinfunction "1_1") (pintype "passive"))
      (node (ref "R41") (pin "1") (pinfunction "1_1") (pintype "passive"))
      (node (ref "R42") (pin "1") (pinfunction "1_1") (pintype "passive"))
      (node (ref "R73") (pin "2") (pinfunction "2_2") (pintype "passive"))
      (node (ref "R74") (pin "1") (pinfunction "1_1") (pintype "passive"))
      (node (ref "R89") (pin "1") (pinfunction "1_1") (pintype "passive"))
      (node (ref "U23") (pin "14") (pinfunction "TEST_14") (pintype "input"))
      (node (ref "U23") (pin "40") (pinfunction "SEL48_40") (pintype "input"))
      (node (ref "U23") (pin "EPAD") (pinfunction "VSS_EPAD") (pintype "passive"))
      (node (ref "U6") (pin "10") (pinfunction "TEST_10") (pintype "input"))
      (node (ref "U6") (pin "21") (pinfunction "GND_21") (pintype "power_in"))
      (node (ref "U6") (pin "41") (pinfunction "GND_41") (pintype "power_in"))
      (node (ref "U6") (pin "45") (pinfunction "GND_45") (pintype "power_in"))
      (node (ref "U6") (pin "EPAD") (pinfunction "GND_EPAD") (pintype "power_in"))
      (node (ref "X2") (pin "2") (pintype "passive"))
      (node (ref "X2") (pin "4") (pintype "passive"))
      (node (ref "X3") (pin "2") (pintype "passive"))
      (node (ref "X3") (pin "4") (pintype "passive"))
    )
    (net (code "38") (name "Net-(J12-SHLD)") (class "Default")
      (node (ref "FB10") (pin "2") (pinfunction "2_2") (pintype "passive"))
      (node (ref "J12") (pin "6") (pinfunction "SHLD_6") (pintype "passive"))
    )
    (net (code "39") (name "Net-(J12-VBUS)") (class "Default")
      (node (ref "FB9") (pin "1") (pinfunction "1_1") (pintype "passive"))
      (node (ref "J12") (pin "1") (pinfunction "VBUS_1") (pintype "power_in"))
    )
    (net (code "40") (name "Net-(Q14B-D2)") (class "Default")
      (node (ref "C144") (pin "2") (pinfunction "2_2") (pintype "passive"))
      (node (ref "Q14") (pin "3") (pinfunction "D2_3") (pintype "passive"))
      (node (ref "R45") (pin "2") (pinfunction "2_2") (pintype "passive"))
      (node (ref "U6") (pin "11") (pinfunction "nRESET_11") (pintype "input"))
    )
    (net (code "41") (name "Net-(Q14B-G2)") (class "Default")
      (node (ref "NC8") (pin "1") (pinfunction "1_1") (pintype "passive"))
      (node (ref "Q14") (pin "5") (pinfunction "G2_5") (pintype "passive"))
    )
    (net (code "42") (name "Net-(Q21A-D1)") (class "Default")
      (node (ref "Q21") (pin "5") (pinfunction "G2_5") (pintype "passive"))
      (node (ref "Q21") (pin "6") (pinfunction "D1_6") (pintype "passive"))
      (node (ref "R90") (pin "2") (pinfunction "2_2") (pintype "passive"))
    )
    (net (code "43") (name "Net-(Q21B-D2)") (class "Default")
      (node (ref "FB2") (pin "2") (pinfunction "2_2") (pintype "passive"))
      (node (ref "Q21") (pin "3") (pinfunction "D2_3") (pintype "passive"))
    )
    (net (code "44") (name "Net-(Q25B-D2)") (class "Default")
      (node (ref "Q25") (pin "3") (pinfunction "D2_3") (pintype "passive"))
      (node (ref "R127") (pin "2") (pinfunction "2_2") (pintype "passive"))
      (node (ref "U23") (pin "34") (pinfunction "nRESET_34") (pintype "input"))
    )
    (net (code "45") (name "Net-(Q25B-G2)") (class "Default")
      (node (ref "NC11") (pin "1") (pinfunction "1_1") (pintype "passive"))
      (node (ref "Q25") (pin "5") (pinfunction "G2_5") (pintype "passive"))
    )
    (net (code "46") (name "Net-(U6-OSCI)") (class "Default")
      (node (ref "C146") (pin "1") (pinfunction "1_1") (pintype "passive"))
      (node (ref "U6") (pin "3") (pinfunction "OSCI_3") (pintype "input"))
      (node (ref "X3") (pin "3") (pintype "passive"))
    )
    (net (code "47") (name "Net-(U6-OSCO)") (class "Default")
      (node (ref "C145") (pin "1") (pinfunction "1_1") (pintype "passive"))
      (node (ref "U6") (pin "4") (pinfunction "OSCO_4") (pintype "output"))
      (node (ref "X3") (pin "1") (pintype "passive"))
    )
    (net (code "48") (name "Net-(U6-REF)") (class "Default")
      (node (ref "R74") (pin "2") (pinfunction "2_2") (pintype "passive"))
      (node (ref "U6") (pin "6") (pinfunction "REF_6") (pintype "passive"))
    )
    (net (code "49") (name "Net-(U6-VPHY)") (class "Default")
      (node (ref "C41") (pin "1") (pinfunction "1_1") (pintype "passive"))
      (node (ref "C42") (pin "2") (pinfunction "2_2") (pintype "passive"))
      (node (ref "FB12") (pin "1") (pinfunction "1_1") (pintype "passive"))
      (node (ref "U6") (pin "5") (pinfunction "VPHY_5") (pintype "power_in"))
    )
    (net (code "50") (name "Net-(U6-VPLL)") (class "Default")
      (node (ref "C32") (pin "1") (pinfunction "1_1") (pintype "passive"))
      (node (ref "C33") (pin "2") (pinfunction "2_2") (pintype "passive"))
      (node (ref "FB11") (pin "1") (pinfunction "1_1") (pintype "passive"))
      (node (ref "U6") (pin "9") (pinfunction "VPLL_9") (pintype "power_in"))
    )
    (net (code "51") (name "Net-(U23-CFG_SEL2)") (class "Default")
      (node (ref "R73") (pin "1") (pinfunction "1_1") (pintype "passive"))
      (node (ref "U23") (pin "33") (pinfunction "CFG_SEL2_33") (pintype "bidirectional"))
    )
    (net (code "52") (name "Net-(U23-CRFILT)") (class "Default")
      (node (ref "C89") (pin "1") (pinfunction "1_1") (pintype "passive"))
      (node (ref "U23") (pin "17") (pinfunction "CRFILT_17") (pintype "passive"))
    )
    (net (code "53") (name "Net-(U23-HS_IND{slash}CFG_SEL1)") (class "Default")
      (node (ref "R110") (pin "1") (pinfunction "1_1") (pintype "passive"))
      (node (ref "U23") (pin "32") (pinfunction "HS_IND/CFG_SEL1_32") (pintype "bidirectional"))
    )
    (net (code "54") (name "Net-(U23-LED_A_N1{slash}PRTSWP1)") (class "Default")
      (node (ref "R9") (pin "2") (pinfunction "2_2") (pintype "passive"))
      (node (ref "U23") (pin "37") (pinfunction "LED_A_N1/PRTSWP1_37") (pintype "bidirectional"))
    )
    (net (code "55") (name "Net-(U23-LED_A_N2{slash}PRTSWP2)") (class "Default")
      (node (ref "R27") (pin "2") (pinfunction "2_2") (pintype "passive"))
      (node (ref "U23") (pin "25") (pinfunction "LED_A_N2/PRTSWP2_25") (pintype "bidirectional"))
    )
    (net (code "56") (name "Net-(U23-LED_A_N3{slash}PRTSWP3)") (class "Default")
      (node (ref "R30") (pin "2") (pinfunction "2_2") (pintype "passive"))
      (node (ref "U23") (pin "23") (pinfunction "LED_A_N3/PRTSWP3_23") (pintype "bidirectional"))
    )
    (net (code "57") (name "Net-(U23-LED_A_N4{slash}PRTSWP4)") (class "Default")
      (node (ref "R35") (pin "2") (pinfunction "2_2") (pintype "passive"))
      (node (ref "U23") (pin "13") (pinfunction "LED_A_N4/PRTSWP4_13") (pintype "output"))
    )
    (net (code "58") (name "Net-(U23-LED_B_N1{slash}BOOST0)") (class "Default")
      (node (ref "R40") (pin "2") (pinfunction "2_2") (pintype "passive"))
      (node (ref "U23") (pin "36") (pinfunction "LED_B_N1/BOOST0_36") (pintype "input"))
    )
    (net (code "59") (name "Net-(U23-LED_B_N2{slash}BOOST1)") (class "Default")
      (node (ref "R41") (pin "2") (pinfunction "2_2") (pintype "passive"))
      (node (ref "U23") (pin "24") (pinfunction "LED_B_N2/BOOST1_24") (pintype "input"))
    )
    (net (code "60") (name "Net-(U23-LED_B_N3{slash}GANG_EN)") (class "Default")
      (node (ref "R42") (pin "2") (pinfunction "2_2") (pintype "passive"))
      (node (ref "U23") (pin "22") (pinfunction "LED_B_N3/GANG_EN_22") (pintype "bidirectional"))
    )
    (net (code "61") (name "Net-(U23-LOCAL_PWR{slash}NON_REM0)") (class "Default")
      (node (ref "R102") (pin "2") (pinfunction "2_2") (pintype "passive"))
      (node (ref "U23") (pin "39") (pinfunction "LOCAL_PWR/NON_REM0_39") (pintype "input"))
    )
    (net (code "62") (name "Net-(U23-OCS_N1)") (class "Default")
      (node (ref "R91") (pin "1") (pinfunction "1_1") (pintype "passive"))
      (node (ref "U23") (pin "16") (pinfunction "OCS_N1_16") (pintype "input"))
    )
    (net (code "63") (name "Net-(U23-OCS_N2)") (class "Default")
      (node (ref "R94") (pin "2") (pinfunction "2_2") (pintype "passive"))
      (node (ref "U23") (pin "20") (pinfunction "OCS_N2_20") (pintype "input"))
    )
    (net (code "64") (name "Net-(U23-OCS_N3)") (class "Default")
      (node (ref "R99") (pin "2") (pinfunction "2_2") (pintype "passive"))
      (node (ref "U23") (pin "26") (pinfunction "OCS_N3_26") (pintype "input"))
    )
    (net (code "65") (name "Net-(U23-OCS_N4)") (class "Default")
      (node (ref "R29") (pin "1") (pinfunction "1_1") (pintype "passive"))
      (node (ref "U23") (pin "28") (pinfunction "OCS_N4_28") (pintype "input"))
    )
    (net (code "66") (name "Net-(U23-PLLFILT)") (class "Default")
      (node (ref "C90") (pin "1") (pinfunction "1_1") (pintype "passive"))
      (node (ref "U23") (pin "46") (pinfunction "PLLFILT_46") (pintype "passive"))
    )
    (net (code "67") (name "Net-(U23-RBIAS)") (class "Default")
      (node (ref "R89") (pin "2") (pinfunction "2_2") (pintype "passive"))
      (node (ref "U23") (pin "47") (pinfunction "RBIAS_47") (pintype "passive"))
    )
    (net (code "68") (name "Net-(U23-SCL{slash}SMBCLK{slash}CFG_SEL0)") (class "Default")
      (node (ref "R106") (pin "1") (pinfunction "1_1") (pintype "passive"))
      (node (ref "U23") (pin "31") (pinfunction "SCL/SMBCLK/CFG_SEL0_31") (pintype "bidirectional"))
    )
    (net (code "69") (name "Net-(U23-SDA{slash}SMBDATA{slash}NON_REM1)") (class "Default")
      (node (ref "R95") (pin "2") (pinfunction "2_2") (pintype "passive"))
      (node (ref "U23") (pin "29") (pinfunction "SDA/SMBDATA/NON_REM1_29") (pintype "bidirectional"))
    )
    (net (code "70") (name "Net-(U23-USBDM_DN4{slash}PRT_DIS_M4)") (class "Default")
      (node (ref "R8") (pin "1") (pinfunction "1_1") (pintype "passive"))
      (node (ref "U23") (pin "8") (pinfunction "USBDM_DN4/PRT_DIS_M4_8") (pintype "bidirectional"))
    )
    (net (code "71") (name "Net-(U23-USBDP_DN4{slash}PRT_DIS_P4)") (class "Default")
      (node (ref "R26") (pin "1") (pinfunction "1_1") (pintype "passive"))
      (node (ref "U23") (pin "9") (pinfunction "USBDP_DN4/PRT_DIS_P4_9") (pintype "bidirectional"))
    )
    (net (code "72") (name "Net-(U23-VBUS_DET)") (class "Default")
      (node (ref "R100") (pin "2") (pinfunction "2_2") (pintype "passive"))
      (node (ref "R101") (pin "1") (pinfunction "1_1") (pintype "passive"))
      (node (ref "U23") (pin "35") (pinfunction "VBUS_DET_35") (pintype "input"))
    )
    (net (code "73") (name "Net-(U23-XTALIN{slash}CLKIN)") (class "Default")
      (node (ref "C88") (pin "1") (pinfunction "1_1") (pintype "passive"))
      (node (ref "R88") (pin "1") (pinfunction "1_1") (pintype "passive"))
      (node (ref "U23") (pin "45") (pinfunction "XTALIN/CLKIN_45") (pintype "input"))
      (node (ref "X2") (pin "3") (pintype "passive"))
    )
    (net (code "74") (name "Net-(U23-XTALOUT)") (class "Default")
      (node (ref "C102") (pin "1") (pinfunction "1_1") (pintype "passive"))
      (node (ref "R88") (pin "2") (pinfunction "2_2") (pintype "passive"))
      (node (ref "U23") (pin "44") (pinfunction "XTALOUT_44") (pintype "output"))
      (node (ref "X2") (pin "1") (pintype "passive"))
    )
    (net (code "75") (name "VBUS") (class "Default")
      (node (ref "C132") (pin "2") (pinfunction "2_2") (pintype "passive"))
      (node (ref "D28") (pin "6") (pinfunction "Vcc_6") (pintype "power_in"))
      (node (ref "FB9") (pin "2") (pinfunction "2_2") (pintype "passive"))
      (node (ref "Q21") (pin "2") (pinfunction "G1_2") (pintype "passive"))
      (node (ref "R100") (pin "1") (pinfunction "1_1") (pintype "passive"))
      (node (ref "TP49") (pin "1") (pintype "passive"))
    )
    (net (code "76") (name "unconnected-(D28-IO3-Pad4)") (class "Default")
      (node (ref "D28") (pin "4") (pinfunction "IO3_4") (pintype "passive+no_connect"))
    )
    (net (code "77") (name "unconnected-(D28-NC-Pad5)") (class "Default")
      (node (ref "D28") (pin "5") (pinfunction "NC_5") (pintype "passive+no_connect"))
    )
    (net (code "78") (name "unconnected-(J12-ID-Pad4)") (class "Default")
      (node (ref "J12") (pin "4") (pinfunction "ID_4") (pintype "passive+no_connect"))
    )
    (net (code "79") (name "unconnected-(Q14A-D1-Pad6)") (class "Default")
      (node (ref "Q14") (pin "6") (pinfunction "D1_6") (pintype "passive+no_connect"))
    )
    (net (code "80") (name "unconnected-(U6-ADBUS4-Pad17)") (class "Default")
      (node (ref "U6") (pin "17") (pinfunction "ADBUS4_17") (pintype "bidirectional+no_connect"))
    )
    (net (code "81") (name "unconnected-(U6-ADBUS5-Pad18)") (class "Default")
      (node (ref "U6") (pin "18") (pinfunction "ADBUS5_18") (pintype "bidirectional+no_connect"))
    )
    (net (code "82") (name "unconnected-(U6-ADBUS6-Pad19)") (class "Default")
      (node (ref "U6") (pin "19") (pinfunction "ADBUS6_19") (pintype "bidirectional+no_connect"))
    )
    (net (code "83") (name "unconnected-(U6-ADBUS7-Pad20)") (class "Default")
      (node (ref "U6") (pin "20") (pinfunction "ADBUS7_20") (pintype "bidirectional+no_connect"))
    )
    (net (code "84") (name "unconnected-(U6-BDBUS4-Pad26)") (class "Default")
      (node (ref "U6") (pin "26") (pinfunction "BDBUS4_26") (pintype "bidirectional+no_connect"))
    )
    (net (code "85") (name "unconnected-(U6-BDBUS5-Pad27)") (class "Default")
      (node (ref "U6") (pin "27") (pinfunction "BDBUS5_27") (pintype "bidirectional+no_connect"))
    )
    (net (code "86") (name "unconnected-(U6-BDBUS6-Pad28)") (class "Default")
      (node (ref "U6") (pin "28") (pinfunction "BDBUS6_28") (pintype "bidirectional+no_connect"))
    )
    (net (code "87") (name "unconnected-(U6-BDBUS7-Pad29)") (class "Default")
      (node (ref "U6") (pin "29") (pinfunction "BDBUS7_29") (pintype "bidirectional+no_connect"))
    )
    (net (code "88") (name "unconnected-(U6-CDBUS6-Pad39)") (class "Default")
      (node (ref "U6") (pin "39") (pinfunction "CDBUS6_39") (pintype "bidirectional+no_connect"))
    )
    (net (code "89") (name "unconnected-(U6-CDBUS7-Pad40)") (class "Default")
      (node (ref "U6") (pin "40") (pinfunction "CDBUS7_40") (pintype "bidirectional+no_connect"))
    )
    (net (code "90") (name "unconnected-(U6-DDBUS2-Pad47)") (class "Default")
      (node (ref "U6") (pin "47") (pinfunction "DDBUS2_47") (pintype "bidirectional+no_connect"))
    )
    (net (code "91") (name "unconnected-(U6-DDBUS3-Pad48)") (class "Default")
      (node (ref "U6") (pin "48") (pinfunction "DDBUS3_48") (pintype "bidirectional+no_connect"))
    )
    (net (code "92") (name "unconnected-(U6-DDBUS4-Pad49)") (class "Default")
      (node (ref "U6") (pin "49") (pinfunction "DDBUS4_49") (pintype "bidirectional+no_connect"))
    )
    (net (code "93") (name "unconnected-(U6-DDBUS5-Pad51)") (class "Default")
      (node (ref "U6") (pin "51") (pinfunction "DDBUS5_51") (pintype "bidirectional+no_connect"))
    )
    (net (code "94") (name "unconnected-(U6-DDBUS6-Pad52)") (class "Default")
      (node (ref "U6") (pin "52") (pinfunction "DDBUS6_52") (pintype "bidirectional+no_connect"))
    )
    (net (code "95") (name "unconnected-(U6-DDBUS7-Pad53)") (class "Default")
      (node (ref "U6") (pin "53") (pinfunction "DDBUS7_53") (pintype "bidirectional+no_connect"))
    )
    (net (code "96") (name "unconnected-(U6-EECLK-Pad56)") (class "Default")
      (node (ref "U6") (pin "56") (pinfunction "EECLK_56") (pintype "output+no_connect"))
    )
    (net (code "97") (name "unconnected-(U6-EECS-Pad1)") (class "Default")
      (node (ref "U6") (pin "1") (pinfunction "EECS_1") (pintype "bidirectional+no_connect"))
    )
    (net (code "98") (name "unconnected-(U6-EEDATA-Pad55)") (class "Default")
      (node (ref "U6") (pin "55") (pinfunction "EEDATA_55") (pintype "bidirectional+no_connect"))
    )
    (net (code "99") (name "unconnected-(U6-nPWREN-Pad54)") (class "Default")
      (node (ref "U6") (pin "54") (pinfunction "nPWREN_54") (pintype "output+no_connect"))
    )
    (net (code "100") (name "unconnected-(U6-nSUSPEND-Pad30)") (class "Default")
      (node (ref "U6") (pin "30") (pinfunction "nSUSPEND_30") (pintype "output+no_connect"))
    )
    (net (code "101") (name "unconnected-(U23-LED_BN4-Pad12)") (class "Default")
      (node (ref "U23") (pin "12") (pinfunction "LED_BN4_12") (pintype "output+no_connect"))
    )
    (net (code "102") (name "unconnected-(U23-NC-Pad11)") (class "Default")
      (node (ref "U23") (pin "11") (pinfunction "NC_11") (pintype "passive+no_connect"))
    )
    (net (code "103") (name "unconnected-(U23-PRTPWR1-Pad15)") (class "Default")
      (node (ref "U23") (pin "15") (pinfunction "PRTPWR1_15") (pintype "output+no_connect"))
    )
    (net (code "104") (name "unconnected-(U23-PRTPWR2-Pad19)") (class "Default")
      (node (ref "U23") (pin "19") (pinfunction "PRTPWR2_19") (pintype "output+no_connect"))
    )
    (net (code "105") (name "unconnected-(U23-PRTPWR3-Pad21)") (class "Default")
      (node (ref "U23") (pin "21") (pinfunction "PRTPWR3_21") (pintype "output+no_connect"))
    )
    (net (code "106") (name "unconnected-(U23-PRTPWR4-Pad27)") (class "Default")
      (node (ref "U23") (pin "27") (pinfunction "PRTPWR4_27") (pintype "output+no_connect"))
    )
  )
)
